# fan-interface-v1_0.net
KiCad netlist of a schematic drawn in EAGLE
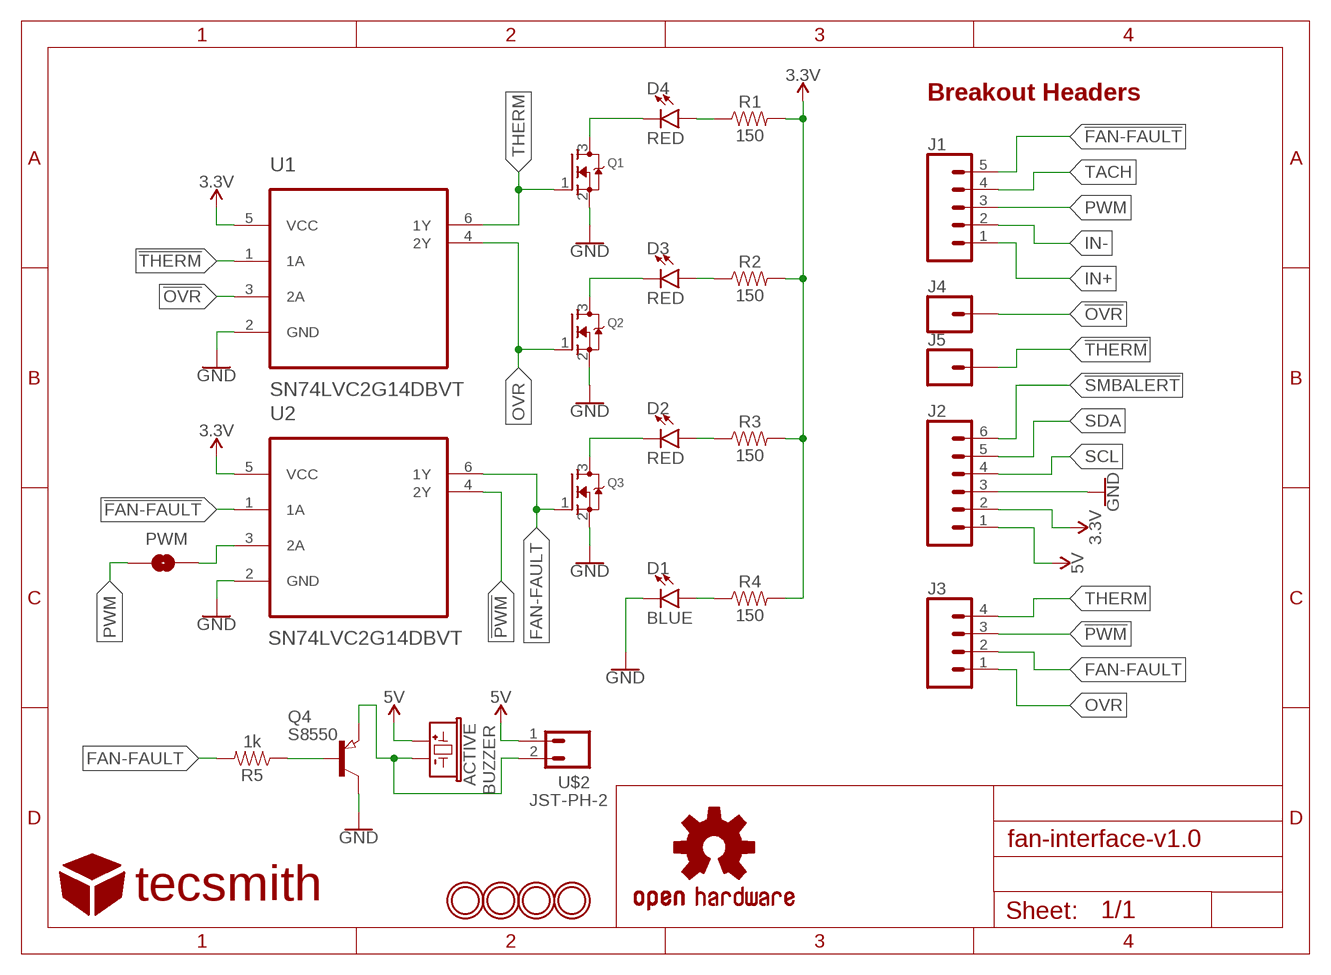
[diagram p0: schematic, sheet 1]

(export (version "E")
  (design (tool "Eeschema 10.0.6"))
  (components
    (comp (ref "ACTIVE")
      (value "BUZZER")
      (footprint "eagle-import:BUZZER-SMD")
      (libsource (lib "eagle-import") (part "BUZZER"))
    )
    (comp (ref "D1")
      (value "BLUE")
      (footprint "eagle-import:LED-0603")
      (libsource (lib "eagle-import") (part "LED-BLUE0603"))
    )
    (comp (ref "D2")
      (value "RED")
      (footprint "eagle-import:LED-0603")
      (libsource (lib "eagle-import") (part "LED-RED0603"))
    )
    (comp (ref "D3")
      (value "RED")
      (footprint "eagle-import:LED-0603")
      (libsource (lib "eagle-import") (part "LED-RED0603"))
    )
    (comp (ref "D4")
      (value "RED")
      (footprint "eagle-import:LED-0603")
      (libsource (lib "eagle-import") (part "LED-RED0603"))
    )
    (comp (ref "J1")
      (value "CONN_05")
      (footprint "eagle-import:1X05")
      (libsource (lib "eagle-import") (part "CONN_05"))
    )
    (comp (ref "J2")
      (value "CONN_06SILK_FEMALE_PTH")
      (footprint "eagle-import:1X06")
      (libsource (lib "eagle-import") (part "CONN_06SILK_FEMALE_PTH"))
    )
    (comp (ref "J3")
      (value "CONN_04PTH")
      (footprint "eagle-import:1X04")
      (libsource (lib "eagle-import") (part "CONN_04PTH"))
    )
    (comp (ref "J4")
      (value "CONN_01")
      (footprint "eagle-import:1X01")
      (libsource (lib "eagle-import") (part "CONN_01"))
    )
    (comp (ref "J5")
      (value "CONN_01")
      (footprint "eagle-import:1X01")
      (libsource (lib "eagle-import") (part "CONN_01"))
    )
    (comp (ref "LOGO1")
      (value "OSHW-LOGOS")
      (footprint "eagle-import:OSHW-LOGO-S")
      (libsource (lib "eagle-import") (part "OSHW-LOGOS"))
    )
    (comp (ref "PWM")
      (value "JUMPER-SMT_2_NO_SILK")
      (footprint "eagle-import:SMT-JUMPER_2_NO_SILK")
      (libsource (lib "eagle-import") (part "JUMPER-SMT_2_NO_SILK"))
    )
    (comp (ref "Q1")
      (value "MOSFET-NREFLOW")
      (footprint "eagle-import:SOT23")
      (libsource (lib "eagle-import") (part "MOSFET-NREFLOW"))
    )
    (comp (ref "Q2")
      (value "MOSFET-NREFLOW")
      (footprint "eagle-import:SOT23")
      (libsource (lib "eagle-import") (part "MOSFET-NREFLOW"))
    )
    (comp (ref "Q3")
      (value "MOSFET-NREFLOW")
      (footprint "eagle-import:SOT23")
      (libsource (lib "eagle-import") (part "MOSFET-NREFLOW"))
    )
    (comp (ref "Q4")
      (value "S8550")
      (footprint "eagle-import:SOT23")
      (libsource (lib "eagle-import") (part "PNP-TRANSISTOR_SOT23"))
    )
    (comp (ref "R1")
      (value "150")
      (footprint "eagle-import:0603")
      (libsource (lib "eagle-import") (part "150OHM-0603-1/10W-1%"))
    )
    (comp (ref "R2")
      (value "150")
      (footprint "eagle-import:0603")
      (libsource (lib "eagle-import") (part "150OHM-0603-1/10W-1%"))
    )
    (comp (ref "R3")
      (value "150")
      (footprint "eagle-import:0603")
      (libsource (lib "eagle-import") (part "150OHM-0603-1/10W-1%"))
    )
    (comp (ref "R4")
      (value "150")
      (footprint "eagle-import:0603")
      (libsource (lib "eagle-import") (part "150OHM-0603-1/10W-1%"))
    )
    (comp (ref "R5")
      (value "1k")
      (footprint "eagle-import:0603")
      (libsource (lib "eagle-import") (part "1KOHM-0603-1/10W-1%"))
    )
    (comp (ref "U$1")
      (value "TECSMITH-LOGO")
      (footprint "eagle-import:TECSMITH-LOGO")
      (libsource (lib "eagle-import") (part "TECSMITH-LOGO"))
    )
    (comp (ref "U$2")
      (value "JST-PH-2")
      (footprint "eagle-import:JST-PH2")
      (libsource (lib "eagle-import") (part "JST-PH-2"))
    )
    (comp (ref "U$7")
      (value "MOUNTINGHOLE2.5")
      (footprint "eagle-import:MOUNTINGHOLE_2.5_PLATED")
      (libsource (lib "eagle-import") (part "MOUNTINGHOLE2.5"))
    )
    (comp (ref "U$8")
      (value "MOUNTINGHOLE2.5")
      (footprint "eagle-import:MOUNTINGHOLE_2.5_PLATED")
      (libsource (lib "eagle-import") (part "MOUNTINGHOLE2.5"))
    )
    (comp (ref "U$9")
      (value "MOUNTINGHOLE2.5")
      (footprint "eagle-import:MOUNTINGHOLE_2.5_PLATED")
      (libsource (lib "eagle-import") (part "MOUNTINGHOLE2.5"))
    )
    (comp (ref "U$10")
      (value "MOUNTINGHOLE2.5")
      (footprint "eagle-import:MOUNTINGHOLE_2.5_PLATED")
      (libsource (lib "eagle-import") (part "MOUNTINGHOLE2.5"))
    )
    (comp (ref "U1")
      (value "SN74LVC2G14DBVT")
      (footprint "eagle-import:SOT95P280X145-6N")
      (libsource (lib "eagle-import") (part "SN74LVC2G14DBVT"))
    )
    (comp (ref "U2")
      (value "SN74LVC2G14DBVT")
      (footprint "eagle-import:SOT95P280X145-6N")
      (libsource (lib "eagle-import") (part "SN74LVC2G14DBVT"))
    )
  )
  (nets
    (net (code "1") (name "/~{FAN-FAULT}") (class "Default")
      (node (ref "J1") (pin "5") (pinfunction "5_5") (pintype "passive"))
      (node (ref "U2") (pin "1") (pinfunction "1A_1") (pintype "input"))
    )
    (net (code "2") (name "/~{OVR}") (class "Default")
      (node (ref "J4") (pin "1") (pinfunction "1_1") (pintype "passive"))
      (node (ref "U1") (pin "3") (pinfunction "2A_3") (pintype "input"))
    )
    (net (code "3") (name "/~{PWM}") (class "Default")
      (node (ref "J3") (pin "3") (pinfunction "3_3") (pintype "passive"))
      (node (ref "U2") (pin "4") (pinfunction "2Y_4") (pintype "output"))
    )
    (net (code "4") (name "/~{SMBALERT}") (class "Default")
      (node (ref "J2") (pin "6") (pinfunction "6_6") (pintype "passive"))
    )
    (net (code "5") (name "/~{THERM}") (class "Default")
      (node (ref "J5") (pin "1") (pinfunction "1_1") (pintype "passive"))
      (node (ref "U1") (pin "1") (pinfunction "1A_1") (pintype "input"))
    )
    (net (code "6") (name "3.3V") (class "Default")
      (node (ref "J2") (pin "2") (pinfunction "2_2") (pintype "passive"))
      (node (ref "R1") (pin "2") (pinfunction "2_2") (pintype "passive"))
      (node (ref "R2") (pin "2") (pinfunction "2_2") (pintype "passive"))
      (node (ref "R3") (pin "2") (pinfunction "2_2") (pintype "passive"))
      (node (ref "R4") (pin "2") (pinfunction "2_2") (pintype "passive"))
      (node (ref "U1") (pin "5") (pinfunction "VCC_5") (pintype "power_in"))
      (node (ref "U2") (pin "5") (pinfunction "VCC_5") (pintype "power_in"))
    )
    (net (code "7") (name "5V") (class "Default")
      (node (ref "ACTIVE") (pin "+") (pinfunction "1_+") (pintype "passive"))
      (node (ref "ACTIVE") (pin "+1") (pinfunction "1_+1") (pintype "passive"))
      (node (ref "J2") (pin "1") (pinfunction "1_1") (pintype "passive"))
      (node (ref "U$2") (pin "1") (pinfunction "1_1") (pintype "passive"))
    )
    (net (code "8") (name "FAN-FAULT") (class "Default")
      (node (ref "J3") (pin "2") (pinfunction "2_2") (pintype "passive"))
      (node (ref "Q3") (pin "1") (pinfunction "G_1") (pintype "bidirectional"))
      (node (ref "R5") (pin "2") (pinfunction "2_2") (pintype "passive"))
      (node (ref "U2") (pin "6") (pinfunction "1Y_6") (pintype "output"))
    )
    (net (code "9") (name "GND") (class "Default")
      (node (ref "D1") (pin "C") (pinfunction "C_C") (pintype "passive"))
      (node (ref "J2") (pin "3") (pinfunction "3_3") (pintype "passive"))
      (node (ref "Q1") (pin "2") (pinfunction "S_2") (pintype "bidirectional"))
      (node (ref "Q2") (pin "2") (pinfunction "S_2") (pintype "bidirectional"))
      (node (ref "Q3") (pin "2") (pinfunction "S_2") (pintype "bidirectional"))
      (node (ref "Q4") (pin "3") (pinfunction "C_3") (pintype "passive"))
      (node (ref "U1") (pin "2") (pinfunction "GND_2") (pintype "passive"))
      (node (ref "U2") (pin "2") (pinfunction "GND_2") (pintype "passive"))
    )
    (net (code "10") (name "IN+") (class "Default")
      (node (ref "J1") (pin "1") (pinfunction "1_1") (pintype "passive"))
    )
    (net (code "11") (name "IN-") (class "Default")
      (node (ref "J1") (pin "2") (pinfunction "2_2") (pintype "passive"))
    )
    (net (code "12") (name "Net-(D1-PadA)") (class "Default")
      (node (ref "D1") (pin "A") (pinfunction "A_A") (pintype "passive"))
      (node (ref "R4") (pin "1") (pinfunction "1_1") (pintype "passive"))
    )
    (net (code "13") (name "Net-(D2-PadA)") (class "Default")
      (node (ref "D2") (pin "A") (pinfunction "A_A") (pintype "passive"))
      (node (ref "R3") (pin "1") (pinfunction "1_1") (pintype "passive"))
    )
    (net (code "14") (name "Net-(D3-PadA)") (class "Default")
      (node (ref "D3") (pin "A") (pinfunction "A_A") (pintype "passive"))
      (node (ref "R2") (pin "1") (pinfunction "1_1") (pintype "passive"))
    )
    (net (code "15") (name "Net-(D4-PadA)") (class "Default")
      (node (ref "D4") (pin "A") (pinfunction "A_A") (pintype "passive"))
      (node (ref "R1") (pin "1") (pinfunction "1_1") (pintype "passive"))
    )
    (net (code "16") (name "Net-(Q1-D)") (class "Default")
      (node (ref "D4") (pin "C") (pinfunction "C_C") (pintype "passive"))
      (node (ref "Q1") (pin "3") (pinfunction "D_3") (pintype "bidirectional"))
    )
    (net (code "17") (name "Net-(Q2-D)") (class "Default")
      (node (ref "D3") (pin "C") (pinfunction "C_C") (pintype "passive"))
      (node (ref "Q2") (pin "3") (pinfunction "D_3") (pintype "bidirectional"))
    )
    (net (code "18") (name "Net-(Q3-D)") (class "Default")
      (node (ref "D2") (pin "C") (pinfunction "C_C") (pintype "passive"))
      (node (ref "Q3") (pin "3") (pinfunction "D_3") (pintype "bidirectional"))
    )
    (net (code "19") (name "Net-(Q4-B)") (class "Default")
      (node (ref "Q4") (pin "1") (pinfunction "B_1") (pintype "passive"))
      (node (ref "R5") (pin "1") (pinfunction "1_1") (pintype "passive"))
    )
    (net (code "20") (name "Net-(Q4-E)") (class "Default")
      (node (ref "ACTIVE") (pin "-") (pinfunction "2_-") (pintype "passive"))
      (node (ref "ACTIVE") (pin "-1") (pinfunction "2_-1") (pintype "passive"))
      (node (ref "Q4") (pin "2") (pinfunction "E_2") (pintype "passive"))
      (node (ref "U$2") (pin "2") (pinfunction "2_2") (pintype "passive"))
    )
    (net (code "21") (name "Net-(U2-2A)") (class "Default")
      (node (ref "PWM") (pin "2") (pinfunction "2_2") (pintype "passive"))
      (node (ref "U2") (pin "3") (pinfunction "2A_3") (pintype "input"))
    )
    (net (code "22") (name "OVR") (class "Default")
      (node (ref "J3") (pin "1") (pinfunction "1_1") (pintype "passive"))
      (node (ref "Q2") (pin "1") (pinfunction "G_1") (pintype "bidirectional"))
      (node (ref "U1") (pin "4") (pinfunction "2Y_4") (pintype "output"))
    )
    (net (code "23") (name "PWM") (class "Default")
      (node (ref "J1") (pin "3") (pinfunction "3_3") (pintype "passive"))
      (node (ref "PWM") (pin "1") (pinfunction "1_1") (pintype "passive"))
    )
    (net (code "24") (name "SCL") (class "Default")
      (node (ref "J2") (pin "4") (pinfunction "4_4") (pintype "passive"))
    )
    (net (code "25") (name "SDA") (class "Default")
      (node (ref "J2") (pin "5") (pinfunction "5_5") (pintype "passive"))
    )
    (net (code "26") (name "TACH") (class "Default")
      (node (ref "J1") (pin "4") (pinfunction "4_4") (pintype "passive"))
    )
    (net (code "27") (name "THERM") (class "Default")
      (node (ref "J3") (pin "4") (pinfunction "4_4") (pintype "passive"))
      (node (ref "Q1") (pin "1") (pinfunction "G_1") (pintype "bidirectional"))
      (node (ref "U1") (pin "6") (pinfunction "1Y_6") (pintype "output"))
    )
  )
)
